# Controller_Board_Power_Supply.net
KiCad netlist of a schematic drawn in Altium Designer
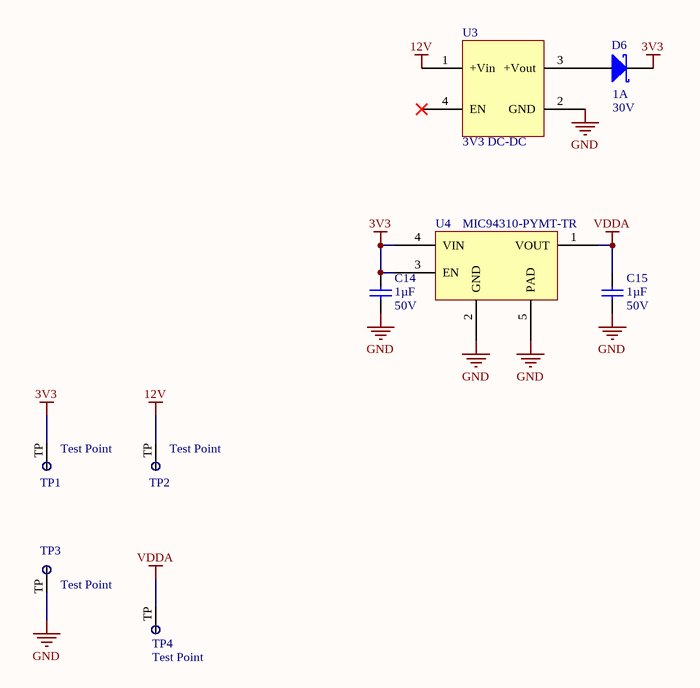
[diagram p0: Controller_Board_Power_Supply.SchDoc]

(export (version "E")
  (design (tool "Eeschema 10.0.6"))
  (components
    (comp (ref "C14")
      (value "CAP CER 1UF 50V 10% X7R 0603")
      (footprint "CAP, 0603")
      (description "1µF ±10% 50V Ceramic Capacitor X7R 0603 (1608 Metric)")
      (fields
        (field (name "TOLERANCE") "±10%")
        (field (name "CAPACITANCE") "1µF")
        (field (name "VOLTAGE") "50V")
      )
      (libsource (lib "Schematic Diagrams") (part "CAP CER 1UF 50V 10% X7R 0603"))
    )
    (comp (ref "C15")
      (value "CAP CER 1UF 50V 10% X7R 0603")
      (footprint "CAP, 0603")
      (description "1µF ±10% 50V Ceramic Capacitor X7R 0603 (1608 Metric)")
      (fields
        (field (name "TOLERANCE") "±10%")
        (field (name "CAPACITANCE") "1µF")
        (field (name "VOLTAGE") "50V")
      )
      (libsource (lib "Schematic Diagrams") (part "CAP CER 1UF 50V 10% X7R 0603"))
    )
    (comp (ref "D6")
      (value "DIODE SCHOTTKY 30V 1A POWERDI123")
      (footprint "DIODE SCHOTTKY 30V 1A POWERDI123")
      (description "Diode Schottky 30V 1A Surface Mount PowerDI™ 123")
      (fields
        (field (name "MANUFACTURER") "Diodes Incorporated")
        (field (name "MANUFACTURER PART NUMBER") "DFLS130L-7")
        (field (name "CURRENT - AVERAGE RECTIFIED (IO)") "1A")
        (field (name "VOLTAGE - DC REVERSE (VR) (MAX)") "30V")
      )
      (libsource (lib "Schematic Diagrams") (part "DIODE SCHOTTKY 30V 1A POWERDI123"))
    )
    (comp (ref "TP1")
      (value "Test Point")
      (footprint "Test Point")
      (libsource (lib "Schematic Diagrams") (part "Test Point"))
    )
    (comp (ref "TP2")
      (value "Test Point")
      (footprint "Test Point")
      (libsource (lib "Schematic Diagrams") (part "Test Point"))
    )
    (comp (ref "TP3")
      (value "Test Point")
      (footprint "Test Point")
      (libsource (lib "Schematic Diagrams") (part "Test Point"))
    )
    (comp (ref "TP4")
      (value "Test Point")
      (footprint "Test Point")
      (libsource (lib "Schematic Diagrams") (part "Test Point"))
    )
    (comp (ref "U3")
      (value "IC DCDC 3.3V 0.5A 4-SMD")
      (footprint "IC DCDC 3.3V 0.5A 4-SMD")
      (description "Non-isolated PoL DC-DC Module 3.3V Output 0.5A 5-36V Input")
      (fields
        (field (name "MANUFACTURER") "Recom Power")
        (field (name "MANUFACTURER PART NUMBER") "ROF-78E3.3-0.5SMD-R")
      )
      (libsource (lib "Schematic Diagrams") (part "IC DCDC 3.3V 0.5A 4-SMD"))
    )
    (comp (ref "U4")
      (value "IC REG LDO 3V 0.2A 4-TDFN")
      (footprint "IC REG LDO 3V 0.2A 4-TDFN")
      (fields
        (field (name "MANUFACTURER") "Microchip Technology")
        (field (name "MANUFACTURER PART NUMBER") "MIC94310-PYMT-TR")
      )
      (libsource (lib "Schematic Diagrams") (part "IC REG LDO 3V 0.2A 4-TDFN"))
    )
  )
  (nets
    (net (code "1") (name "3V3") (class "Default")
      (node (ref "C14") (pin "1") (pinfunction "1_1") (pintype "passive"))
      (node (ref "D6") (pin "2") (pinfunction "K_2") (pintype "passive"))
      (node (ref "TP1") (pin "TP") (pinfunction "1_TP") (pintype "passive"))
      (node (ref "U4") (pin "3") (pinfunction "EN_3") (pintype "passive"))
      (node (ref "U4") (pin "4") (pinfunction "VIN_4") (pintype "passive"))
    )
    (net (code "2") (name "12V") (class "Default")
      (node (ref "TP2") (pin "TP") (pinfunction "1_TP") (pintype "passive"))
      (node (ref "U3") (pin "1") (pinfunction "+Vin_1") (pintype "passive"))
    )
    (net (code "3") (name "GND") (class "Default")
      (node (ref "C14") (pin "2") (pinfunction "2_2") (pintype "passive"))
      (node (ref "C15") (pin "2") (pinfunction "2_2") (pintype "passive"))
      (node (ref "TP3") (pin "TP") (pinfunction "1_TP") (pintype "passive"))
      (node (ref "U3") (pin "2") (pinfunction "GND_2") (pintype "passive"))
      (node (ref "U4") (pin "2") (pinfunction "GND_2") (pintype "passive"))
      (node (ref "U4") (pin "5") (pinfunction "PAD_5") (pintype "passive"))
    )
    (net (code "4") (name "Net-(D6-A)") (class "Default")
      (node (ref "D6") (pin "1") (pinfunction "A_1") (pintype "passive"))
      (node (ref "U3") (pin "3") (pinfunction "+Vout_3") (pintype "passive"))
    )
    (net (code "5") (name "VDDA") (class "Default")
      (node (ref "C15") (pin "1") (pinfunction "1_1") (pintype "passive"))
      (node (ref "TP4") (pin "TP") (pinfunction "1_TP") (pintype "passive"))
      (node (ref "U4") (pin "1") (pinfunction "VOUT_1") (pintype "passive"))
    )
    (net (code "6") (name "unconnected-(U3-EN-Pad4)") (class "Default")
      (node (ref "U3") (pin "4") (pinfunction "EN_4") (pintype "passive+no_connect"))
    )
  )
)
